# MCU.net
KiCad netlist of a schematic drawn in Altium Designer
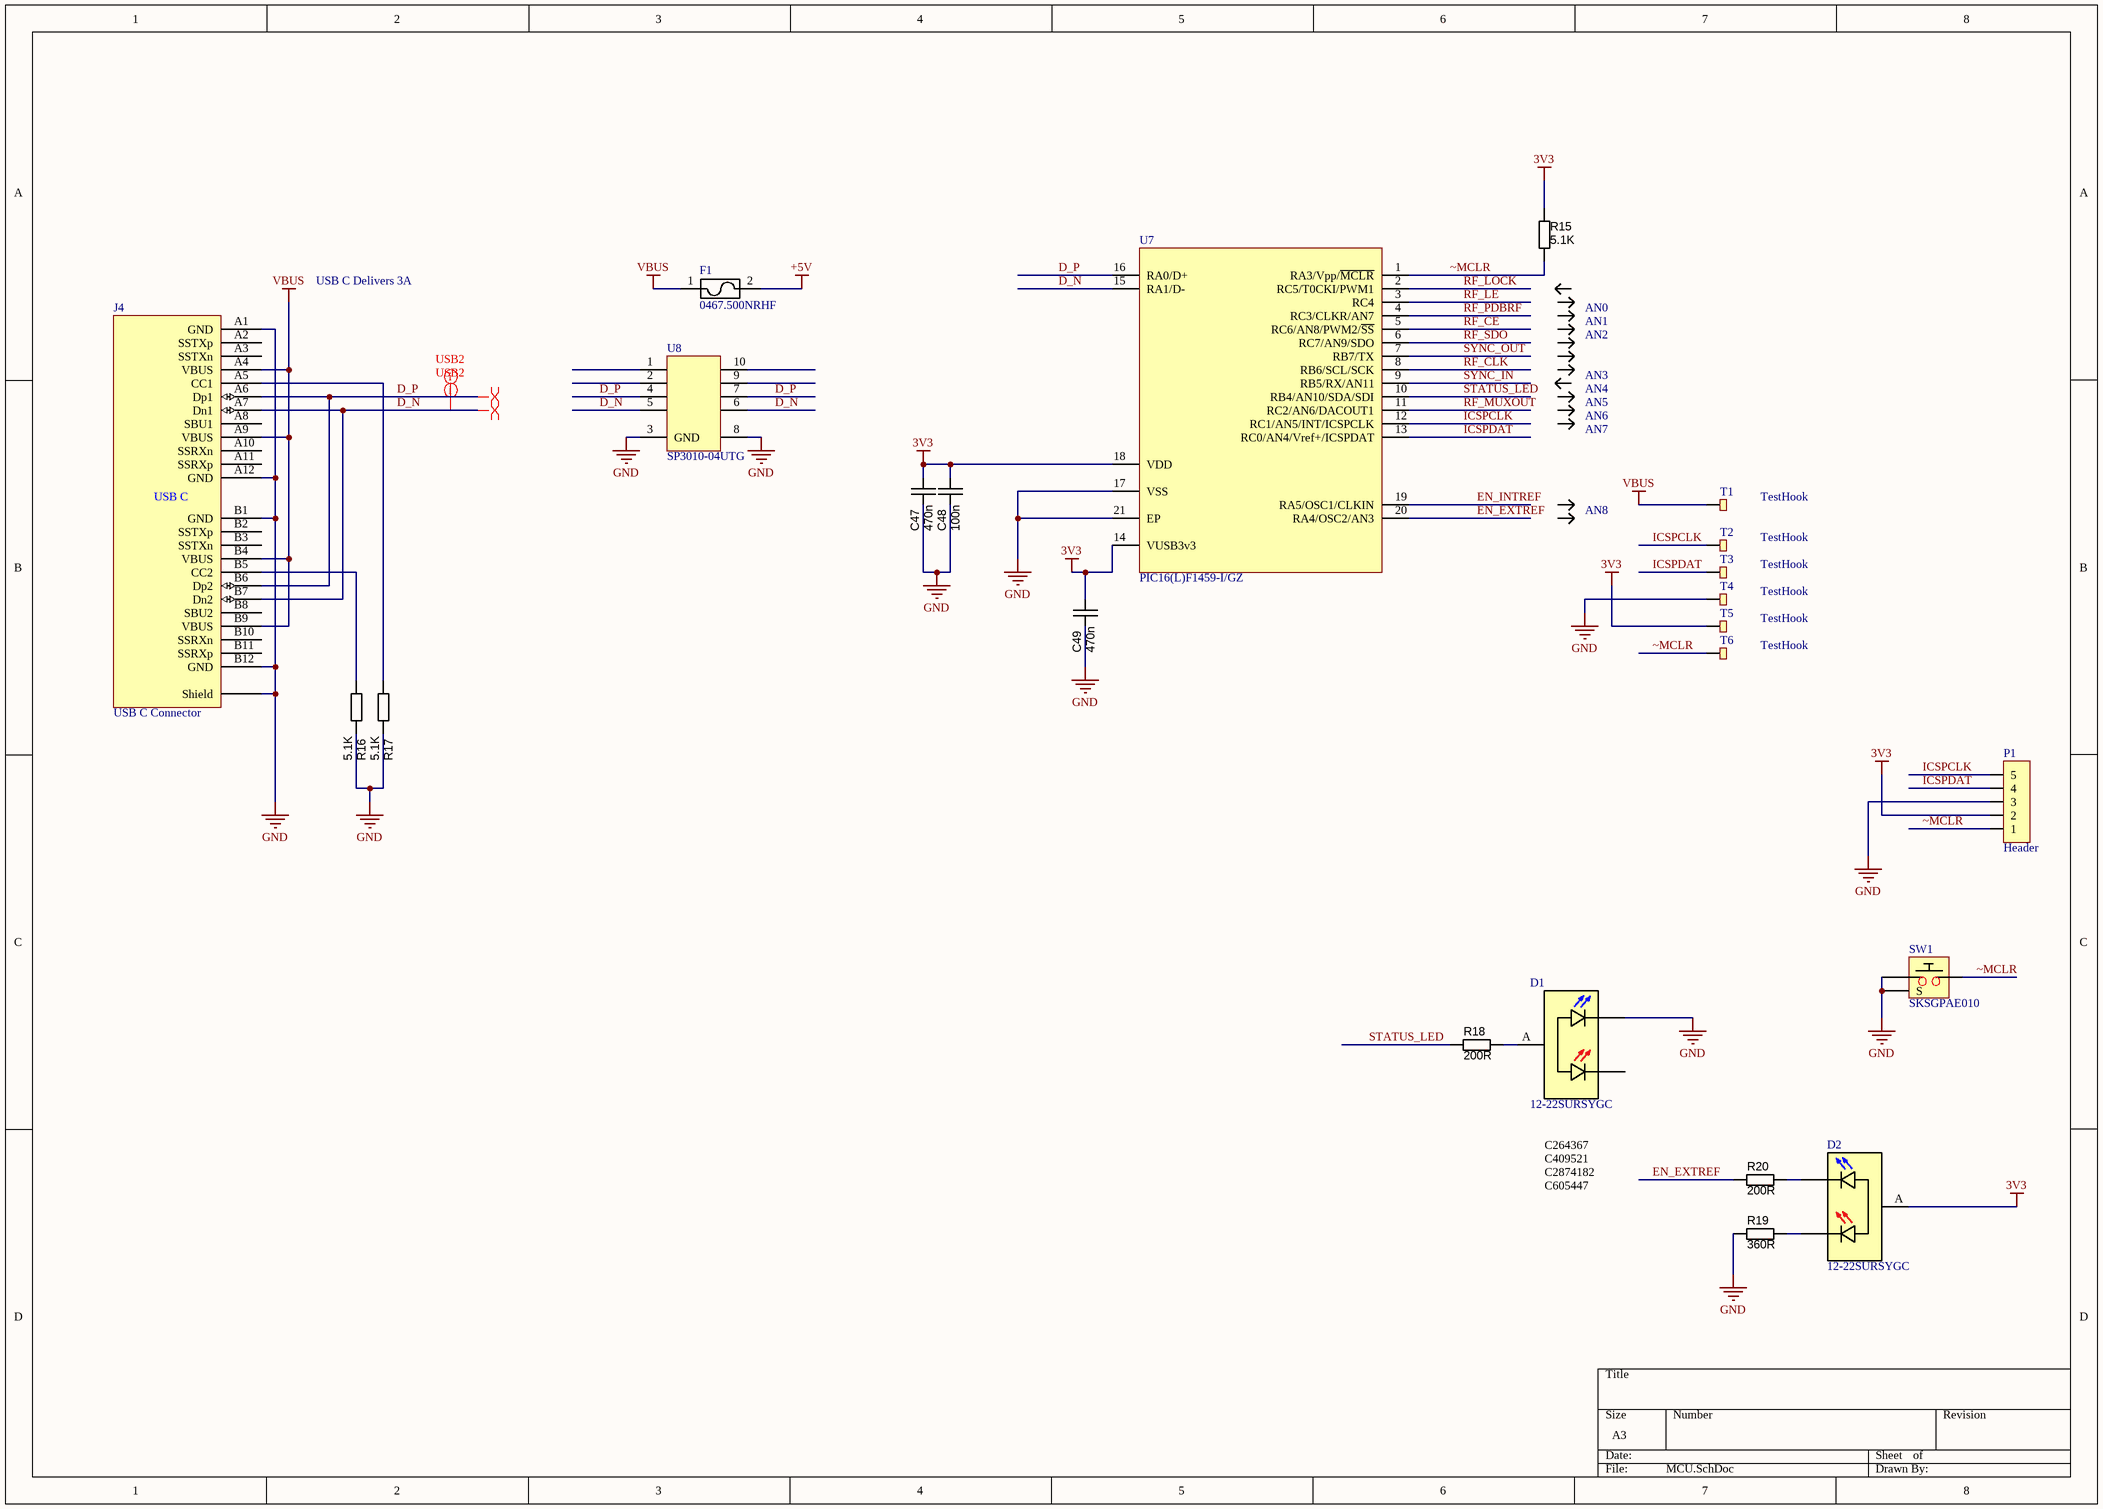
[diagram p0: MCU.SchDoc]

(export (version "E")
  (design (tool "Eeschema 10.0.6"))
  (components
    (comp (ref "C47")
      (value "470n")
      (footprint "CAPC1005N")
      (description "Capacitor SMD Cer 10nF 10% 16V X7R 0402")
      (fields (field (name "TOLERANCE") "±10%"))
      (libsource (lib "PBL - Capacitors") (part "CAPC_10n_0402_16V_10%"))
    )
    (comp (ref "C48")
      (value "100n")
      (footprint "CAPC1005N")
      (description "Capacitor SMD Cer 10nF 10% 16V X7R 0402")
      (fields (field (name "TOLERANCE") "±10%"))
      (libsource (lib "PBL - Capacitors") (part "CAPC_10n_0402_16V_10%"))
    )
    (comp (ref "C49")
      (value "470n")
      (footprint "CAPC1005N")
      (description "Capacitor SMD Cer 10nF 10% 16V X7R 0402")
      (fields (field (name "TOLERANCE") "±10%"))
      (libsource (lib "PBL - Capacitors") (part "CAPC_10n_0402_16V_10%"))
    )
    (comp (ref "D1")
      (value "12-22SURSYGC")
      (footprint "12-22SURSYGC/S530-A2/TR8")
      (description "12-22SURSYGC/S530-A3/E2/TR8")
      (libsource (lib "cvlib") (part "BI_LED"))
    )
    (comp (ref "D2")
      (value "12-22SURSYGC")
      (footprint "12-22SURSYGC/S530-A2/TR8")
      (description "12-22SURSYGC/S530-A3/E2/TR8")
      (libsource (lib "cvlib") (part "BI_LED"))
    )
    (comp (ref "F1")
      (value "0467.500NRHF")
      (footprint "0467005.NRHF")
      (description "0467005.NRHF")
      (libsource (lib "cvlib") (part "Fuse"))
    )
    (comp (ref "J4")
      (value "USB C Connector")
      (footprint "UT11113-11602-7H")
      (description "USB C connector")
      (libsource (lib "cvlib") (part "USB_C"))
    )
    (comp (ref "P1")
      (value "Header")
      (footprint "HEADER5X")
      (description "5 Pin Header")
      (libsource (lib "cvlib") (part "Header_5Pin"))
    )
    (comp (ref "R15")
      (value "5.1K")
      (footprint "RESC1005N")
      (description "Resistor SMD chip 3.3k Ohm 0.063W 5% 0402")
      (fields (field (name "TOLERANCE") "±5%") (field (name "Comment") "Thick Film"))
      (libsource (lib "") (part "RES_3K3_0402_5%_1"))
    )
    (comp (ref "R16")
      (value "5.1K")
      (footprint "RESC1005N")
      (description "Resistor SMD chip 3.3k Ohm 0.063W 5% 0402")
      (fields (field (name "TOLERANCE") "±5%") (field (name "Comment") "Thick Film"))
      (libsource (lib "PBL - Resistors") (part "RES_3K3_0402_5%"))
    )
    (comp (ref "R17")
      (value "5.1K")
      (footprint "RESC1005N")
      (description "Resistor SMD chip 3.3k Ohm 0.063W 5% 0402")
      (fields (field (name "TOLERANCE") "±5%") (field (name "Comment") "Thick Film"))
      (libsource (lib "PBL - Resistors") (part "RES_3K3_0402_5%"))
    )
    (comp (ref "R18")
      (value "200R")
      (footprint "RESC1005N")
      (description "Resistor SMD chip 3.3k Ohm 0.063W 5% 0402")
      (fields (field (name "TOLERANCE") "±5%") (field (name "Comment") "Thick Film"))
      (libsource (lib "") (part "RES_3K3_0402_5%_3"))
    )
    (comp (ref "R19")
      (value "360R")
      (footprint "RESC1005N")
      (description "Resistor SMD chip 3.3k Ohm 0.063W 5% 0402")
      (fields (field (name "TOLERANCE") "±5%") (field (name "Comment") "Thick Film"))
      (libsource (lib "") (part "RES_3K3_0402_5%_2"))
    )
    (comp (ref "R20")
      (value "200R")
      (footprint "RESC1005N")
      (description "Resistor SMD chip 3.3k Ohm 0.063W 5% 0402")
      (fields (field (name "TOLERANCE") "±5%") (field (name "Comment") "Thick Film"))
      (libsource (lib "") (part "RES_3K3_0402_5%_2"))
    )
    (comp (ref "SW1")
      (value "SKSGPAE010")
      (footprint "SKSGPAE010")
      (libsource (lib "cvlib") (part "PushButton_Grounded"))
    )
    (comp (ref "T1")
      (value "TestHook")
      (footprint "Test_PAD_0851-0-15-20-82-14-11-0")
      (libsource (lib "cvlib") (part "TestHook"))
    )
    (comp (ref "T2")
      (value "TestHook")
      (footprint "Test_PAD_0851-0-15-20-82-14-11-0")
      (libsource (lib "cvlib") (part "TestHook"))
    )
    (comp (ref "T3")
      (value "TestHook")
      (footprint "Test_PAD_0851-0-15-20-82-14-11-0")
      (libsource (lib "cvlib") (part "TestHook"))
    )
    (comp (ref "T4")
      (value "TestHook")
      (footprint "Test_PAD_0851-0-15-20-82-14-11-0")
      (libsource (lib "cvlib") (part "TestHook"))
    )
    (comp (ref "T5")
      (value "TestHook")
      (footprint "Test_PAD_0851-0-15-20-82-14-11-0")
      (libsource (lib "cvlib") (part "TestHook"))
    )
    (comp (ref "T6")
      (value "TestHook")
      (footprint "Test_PAD_0851-0-15-20-82-14-11-0")
      (libsource (lib "cvlib") (part "TestHook"))
    )
    (comp (ref "U7")
      (value "PIC16(L)F1459-I/GZ")
      (footprint "QFN20_4x4")
      (libsource (lib "cvlib") (part "PIC16(L)F1459-I/GZ"))
    )
    (comp (ref "U8")
      (value "SP3010-04UTG")
      (footprint "uDFN-10")
      (description "ESD Protection")
      (libsource (lib "cvlib") (part "SP3010-04UTG"))
    )
  )
  (nets
    (net (code "1") (name "+5V") (class "Default") (node (ref "F1") (pin "2") (pintype "passive")))
    (net (code "2") (name "/D_N") (class "Default")
      (node (ref "J4") (pin "A7") (pinfunction "Dn1_A7") (pintype "bidirectional"))
      (node (ref "J4") (pin "B7") (pinfunction "Dn2_B7") (pintype "bidirectional"))
      (node (ref "U7") (pin "15") (pinfunction "RA1/D-_15") (pintype "passive"))
      (node (ref "U8") (pin "5") (pintype "passive"))
      (node (ref "U8") (pin "6") (pintype "passive"))
    )
    (net (code "3") (name "/D_P") (class "Default")
      (node (ref "J4") (pin "A6") (pinfunction "Dp1_A6") (pintype "bidirectional"))
      (node (ref "J4") (pin "B6") (pinfunction "Dp2_B6") (pintype "bidirectional"))
      (node (ref "U7") (pin "16") (pinfunction "RA0/D+_16") (pintype "passive"))
      (node (ref "U8") (pin "4") (pintype "passive"))
      (node (ref "U8") (pin "7") (pintype "passive"))
    )
    (net (code "4") (name "/EN_EXTREF") (class "Default")
      (node (ref "R20") (pin "2") (pinfunction "2_2") (pintype "passive"))
      (node (ref "U7") (pin "20") (pinfunction "RA4/OSC2/AN3_20") (pintype "passive"))
    )
    (net (code "5") (name "/EN_INTREF") (class "Default")
      (node (ref "U7") (pin "19") (pinfunction "RA5/OSC1/CLKIN_19") (pintype "passive"))
    )
    (net (code "6") (name "/ICSPCLK") (class "Default")
      (node (ref "P1") (pin "5") (pinfunction "5_5") (pintype "passive"))
      (node (ref "T2") (pin "1") (pinfunction "TP_1") (pintype "power_in"))
      (node (ref "U7") (pin "12") (pinfunction "RC1/AN5/INT/ICSPCLK_12") (pintype "passive"))
    )
    (net (code "7") (name "/ICSPDAT") (class "Default")
      (node (ref "P1") (pin "4") (pinfunction "4_4") (pintype "passive"))
      (node (ref "T3") (pin "1") (pinfunction "TP_1") (pintype "power_in"))
      (node (ref "U7") (pin "13") (pinfunction "RC0/AN4/Vref+/ICSPDAT_13") (pintype "passive"))
    )
    (net (code "8") (name "/RF_CE") (class "Default")
      (node (ref "U7") (pin "5") (pinfunction "RC6/AN8/PWM2/~{SS}_5") (pintype "passive"))
    )
    (net (code "9") (name "/RF_CLK") (class "Default")
      (node (ref "U7") (pin "8") (pinfunction "RB6/SCL/SCK_8") (pintype "passive"))
    )
    (net (code "10") (name "/RF_LE") (class "Default")
      (node (ref "U7") (pin "3") (pinfunction "RC4_3") (pintype "passive"))
    )
    (net (code "11") (name "/RF_LOCK") (class "Default")
      (node (ref "U7") (pin "2") (pinfunction "RC5/T0CKI/PWM1_2") (pintype "passive"))
    )
    (net (code "12") (name "/RF_MUXOUT") (class "Default")
      (node (ref "U7") (pin "11") (pinfunction "RC2/AN6/DACOUT1_11") (pintype "passive"))
    )
    (net (code "13") (name "/RF_PDBRF") (class "Default")
      (node (ref "U7") (pin "4") (pinfunction "RC3/CLKR/AN7_4") (pintype "passive"))
    )
    (net (code "14") (name "/RF_SDO") (class "Default")
      (node (ref "U7") (pin "6") (pinfunction "RC7/AN9/SDO_6") (pintype "passive"))
    )
    (net (code "15") (name "/STATUS_LED") (class "Default")
      (node (ref "R18") (pin "1") (pinfunction "1_1") (pintype "passive"))
      (node (ref "U7") (pin "10") (pinfunction "RB4/AN10/SDA/SDI_10") (pintype "passive"))
    )
    (net (code "16") (name "/SYNC_IN") (class "Default")
      (node (ref "U7") (pin "9") (pinfunction "RB5/RX/AN11_9") (pintype "passive"))
    )
    (net (code "17") (name "/SYNC_OUT") (class "Default")
      (node (ref "U7") (pin "7") (pinfunction "RB7/TX_7") (pintype "passive"))
    )
    (net (code "18") (name "/~MCLR") (class "Default")
      (node (ref "P1") (pin "1") (pinfunction "1_1") (pintype "passive"))
      (node (ref "R15") (pin "1") (pinfunction "1_1") (pintype "passive"))
      (node (ref "SW1") (pin "2") (pinfunction "P2_2") (pintype "passive"))
      (node (ref "T6") (pin "1") (pinfunction "TP_1") (pintype "power_in"))
      (node (ref "U7") (pin "1") (pinfunction "RA3/Vpp/~{MCLR}_1") (pintype "passive"))
    )
    (net (code "19") (name "3V3") (class "Default")
      (node (ref "C47") (pin "2") (pintype "passive"))
      (node (ref "C48") (pin "2") (pintype "passive"))
      (node (ref "C49") (pin "2") (pintype "passive"))
      (node (ref "D2") (pin "A") (pinfunction "A_A") (pintype "passive"))
      (node (ref "P1") (pin "2") (pinfunction "2_2") (pintype "passive"))
      (node (ref "R15") (pin "2") (pinfunction "2_2") (pintype "passive"))
      (node (ref "T5") (pin "1") (pinfunction "TP_1") (pintype "power_in"))
      (node (ref "U7") (pin "14") (pinfunction "VUSB3v3_14") (pintype "passive"))
      (node (ref "U7") (pin "18") (pinfunction "VDD_18") (pintype "power_in"))
    )
    (net (code "20") (name "GND") (class "Default")
      (node (ref "C47") (pin "1") (pintype "passive"))
      (node (ref "C48") (pin "1") (pintype "passive"))
      (node (ref "C49") (pin "1") (pintype "passive"))
      (node (ref "D1") (pin "C1") (pinfunction "R_C_C1") (pintype "passive"))
      (node (ref "J4") (pin "0") (pinfunction "Shield_0") (pintype "power_in"))
      (node (ref "J4") (pin "A1") (pinfunction "GND_A1") (pintype "power_in"))
      (node (ref "J4") (pin "A12") (pinfunction "GND_A12") (pintype "power_in"))
      (node (ref "J4") (pin "B1") (pinfunction "GND_B1") (pintype "power_in"))
      (node (ref "J4") (pin "B12") (pinfunction "GND_B12") (pintype "power_in"))
      (node (ref "P1") (pin "3") (pinfunction "3_3") (pintype "passive"))
      (node (ref "R16") (pin "2") (pinfunction "2_2") (pintype "passive"))
      (node (ref "R17") (pin "2") (pinfunction "2_2") (pintype "passive"))
      (node (ref "R19") (pin "2") (pinfunction "2_2") (pintype "passive"))
      (node (ref "SW1") (pin "1") (pinfunction "P1_1") (pintype "passive"))
      (node (ref "SW1") (pin "3") (pinfunction "S_3") (pintype "passive"))
      (node (ref "T4") (pin "1") (pinfunction "TP_1") (pintype "power_in"))
      (node (ref "U7") (pin "17") (pinfunction "VSS_17") (pintype "passive"))
      (node (ref "U7") (pin "21") (pinfunction "EP_21") (pintype "passive"))
      (node (ref "U8") (pin "3") (pinfunction "GND_3") (pintype "passive"))
      (node (ref "U8") (pin "8") (pinfunction "GND_8") (pintype "passive"))
    )
    (net (code "21") (name "Net-(D1-PadA)") (class "Default")
      (node (ref "D1") (pin "A") (pinfunction "A_A") (pintype "passive"))
      (node (ref "R18") (pin "2") (pinfunction "2_2") (pintype "passive"))
    )
    (net (code "22") (name "Net-(D2-G_C)") (class "Default")
      (node (ref "D2") (pin "C2") (pinfunction "G_C_C2") (pintype "passive"))
      (node (ref "R19") (pin "1") (pinfunction "1_1") (pintype "passive"))
    )
    (net (code "23") (name "Net-(D2-R_C)") (class "Default")
      (node (ref "D2") (pin "C1") (pinfunction "R_C_C1") (pintype "passive"))
      (node (ref "R20") (pin "1") (pinfunction "1_1") (pintype "passive"))
    )
    (net (code "24") (name "Net-(J4-CC1)") (class "Default")
      (node (ref "J4") (pin "A5") (pinfunction "CC1_A5") (pintype "power_in"))
      (node (ref "R17") (pin "1") (pinfunction "1_1") (pintype "passive"))
    )
    (net (code "25") (name "Net-(J4-CC2)") (class "Default")
      (node (ref "J4") (pin "B5") (pinfunction "CC2_B5") (pintype "power_in"))
      (node (ref "R16") (pin "1") (pinfunction "1_1") (pintype "passive"))
    )
    (net (code "26") (name "VBUS") (class "Default")
      (node (ref "F1") (pin "1") (pintype "passive"))
      (node (ref "J4") (pin "A4") (pinfunction "VBUS_A4") (pintype "power_in"))
      (node (ref "J4") (pin "A9") (pinfunction "VBUS_A9") (pintype "power_in"))
      (node (ref "J4") (pin "B4") (pinfunction "VBUS_B4") (pintype "power_in"))
      (node (ref "J4") (pin "B9") (pinfunction "VBUS_B9") (pintype "power_in"))
      (node (ref "T1") (pin "1") (pinfunction "TP_1") (pintype "power_in"))
    )
    (net (code "27") (name "unconnected-(D1-G_C-PadC2)") (class "Default")
      (node (ref "D1") (pin "C2") (pinfunction "G_C_C2") (pintype "passive"))
    )
    (net (code "28") (name "unconnected-(J4-SBU1-PadA8)") (class "Default")
      (node (ref "J4") (pin "A8") (pinfunction "SBU1_A8") (pintype "power_in"))
    )
    (net (code "29") (name "unconnected-(J4-SBU2-PadB8)") (class "Default")
      (node (ref "J4") (pin "B8") (pinfunction "SBU2_B8") (pintype "power_in"))
    )
    (net (code "30") (name "unconnected-(J4-SSRXn-PadA10)") (class "Default")
      (node (ref "J4") (pin "A10") (pinfunction "SSRXn_A10") (pintype "passive"))
    )
    (net (code "31") (name "unconnected-(J4-SSRXn-PadB10)") (class "Default")
      (node (ref "J4") (pin "B10") (pinfunction "SSRXn_B10") (pintype "passive"))
    )
    (net (code "32") (name "unconnected-(J4-SSRXp-PadA11)") (class "Default")
      (node (ref "J4") (pin "A11") (pinfunction "SSRXp_A11") (pintype "passive"))
    )
    (net (code "33") (name "unconnected-(J4-SSRXp-PadB11)") (class "Default")
      (node (ref "J4") (pin "B11") (pinfunction "SSRXp_B11") (pintype "passive"))
    )
    (net (code "34") (name "unconnected-(J4-SSTXn-PadA3)") (class "Default")
      (node (ref "J4") (pin "A3") (pinfunction "SSTXn_A3") (pintype "passive"))
    )
    (net (code "35") (name "unconnected-(J4-SSTXn-PadB3)") (class "Default")
      (node (ref "J4") (pin "B3") (pinfunction "SSTXn_B3") (pintype "passive"))
    )
    (net (code "36") (name "unconnected-(J4-SSTXp-PadA2)") (class "Default")
      (node (ref "J4") (pin "A2") (pinfunction "SSTXp_A2") (pintype "passive"))
    )
    (net (code "37") (name "unconnected-(J4-SSTXp-PadB2)") (class "Default")
      (node (ref "J4") (pin "B2") (pinfunction "SSTXp_B2") (pintype "passive"))
    )
    (net (code "38") (name "unconnected-(U8-Pad1)") (class "Default")
      (node (ref "U8") (pin "1") (pintype "passive"))
    )
    (net (code "39") (name "unconnected-(U8-Pad2)") (class "Default")
      (node (ref "U8") (pin "2") (pintype "passive"))
    )
    (net (code "40") (name "unconnected-(U8-Pad9)") (class "Default")
      (node (ref "U8") (pin "9") (pintype "passive"))
    )
    (net (code "41") (name "unconnected-(U8-Pad10)") (class "Default")
      (node (ref "U8") (pin "10") (pintype "passive"))
    )
  )
)
